# LED_Fret.net
KiCad netlist of a schematic drawn in Altium Designer
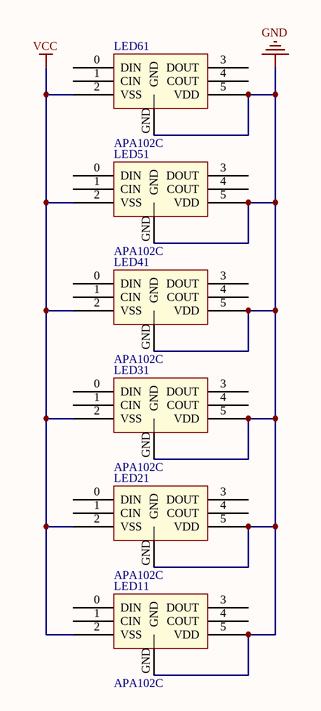
[diagram p0: LED_Fret.SchDoc]

(export (version "E")
  (design (tool "Eeschema 10.0.6"))
  (components
    (comp (ref "LED11")
      (value "APA102C")
      (footprint "RGB LED")
      (libsource (lib "Senior_SCH_Lib") (part "RGB LED"))
    )
    (comp (ref "LED21")
      (value "APA102C")
      (footprint "RGB LED")
      (libsource (lib "Senior_SCH_Lib") (part "RGB LED"))
    )
    (comp (ref "LED31")
      (value "APA102C")
      (footprint "RGB LED")
      (libsource (lib "Senior_SCH_Lib") (part "RGB LED"))
    )
    (comp (ref "LED41")
      (value "APA102C")
      (footprint "RGB LED")
      (libsource (lib "Senior_SCH_Lib") (part "RGB LED"))
    )
    (comp (ref "LED51")
      (value "APA102C")
      (footprint "RGB LED")
      (libsource (lib "Senior_SCH_Lib") (part "RGB LED"))
    )
    (comp (ref "LED61")
      (value "APA102C")
      (footprint "RGB LED")
      (libsource (lib "Senior_SCH_Lib") (part "RGB LED"))
    )
  )
  (nets
    (net (code "1") (name "GND") (class "Default")
      (node (ref "LED11") (pin "5") (pinfunction "VDD_5") (pintype "passive"))
      (node (ref "LED11") (pin "GND") (pinfunction "GND_GND") (pintype "passive"))
      (node (ref "LED21") (pin "5") (pinfunction "VDD_5") (pintype "passive"))
      (node (ref "LED21") (pin "GND") (pinfunction "GND_GND") (pintype "passive"))
      (node (ref "LED31") (pin "5") (pinfunction "VDD_5") (pintype "passive"))
      (node (ref "LED31") (pin "GND") (pinfunction "GND_GND") (pintype "passive"))
      (node (ref "LED41") (pin "5") (pinfunction "VDD_5") (pintype "passive"))
      (node (ref "LED41") (pin "GND") (pinfunction "GND_GND") (pintype "passive"))
      (node (ref "LED51") (pin "5") (pinfunction "VDD_5") (pintype "passive"))
      (node (ref "LED51") (pin "GND") (pinfunction "GND_GND") (pintype "passive"))
      (node (ref "LED61") (pin "5") (pinfunction "VDD_5") (pintype "passive"))
      (node (ref "LED61") (pin "GND") (pinfunction "GND_GND") (pintype "passive"))
    )
    (net (code "2") (name "VCC") (class "Default")
      (node (ref "LED11") (pin "2") (pinfunction "VSS_2") (pintype "passive"))
      (node (ref "LED21") (pin "2") (pinfunction "VSS_2") (pintype "passive"))
      (node (ref "LED31") (pin "2") (pinfunction "VSS_2") (pintype "passive"))
      (node (ref "LED41") (pin "2") (pinfunction "VSS_2") (pintype "passive"))
      (node (ref "LED51") (pin "2") (pinfunction "VSS_2") (pintype "passive"))
      (node (ref "LED61") (pin "2") (pinfunction "VSS_2") (pintype "passive"))
    )
    (net (code "3") (name "unconnected-(LED11-CIN-Pad1)") (class "Default")
      (node (ref "LED11") (pin "1") (pinfunction "CIN_1") (pintype "passive"))
    )
    (net (code "4") (name "unconnected-(LED11-COUT-Pad4)") (class "Default")
      (node (ref "LED11") (pin "4") (pinfunction "COUT_4") (pintype "passive"))
    )
    (net (code "5") (name "unconnected-(LED11-DIN-Pad0)") (class "Default")
      (node (ref "LED11") (pin "0") (pinfunction "DIN_0") (pintype "passive"))
    )
    (net (code "6") (name "unconnected-(LED11-DOUT-Pad3)") (class "Default")
      (node (ref "LED11") (pin "3") (pinfunction "DOUT_3") (pintype "passive"))
    )
    (net (code "7") (name "unconnected-(LED21-CIN-Pad1)") (class "Default")
      (node (ref "LED21") (pin "1") (pinfunction "CIN_1") (pintype "passive"))
    )
    (net (code "8") (name "unconnected-(LED21-COUT-Pad4)") (class "Default")
      (node (ref "LED21") (pin "4") (pinfunction "COUT_4") (pintype "passive"))
    )
    (net (code "9") (name "unconnected-(LED21-DIN-Pad0)") (class "Default")
      (node (ref "LED21") (pin "0") (pinfunction "DIN_0") (pintype "passive"))
    )
    (net (code "10") (name "unconnected-(LED21-DOUT-Pad3)") (class "Default")
      (node (ref "LED21") (pin "3") (pinfunction "DOUT_3") (pintype "passive"))
    )
    (net (code "11") (name "unconnected-(LED31-CIN-Pad1)") (class "Default")
      (node (ref "LED31") (pin "1") (pinfunction "CIN_1") (pintype "passive"))
    )
    (net (code "12") (name "unconnected-(LED31-COUT-Pad4)") (class "Default")
      (node (ref "LED31") (pin "4") (pinfunction "COUT_4") (pintype "passive"))
    )
    (net (code "13") (name "unconnected-(LED31-DIN-Pad0)") (class "Default")
      (node (ref "LED31") (pin "0") (pinfunction "DIN_0") (pintype "passive"))
    )
    (net (code "14") (name "unconnected-(LED31-DOUT-Pad3)") (class "Default")
      (node (ref "LED31") (pin "3") (pinfunction "DOUT_3") (pintype "passive"))
    )
    (net (code "15") (name "unconnected-(LED41-CIN-Pad1)") (class "Default")
      (node (ref "LED41") (pin "1") (pinfunction "CIN_1") (pintype "passive"))
    )
    (net (code "16") (name "unconnected-(LED41-COUT-Pad4)") (class "Default")
      (node (ref "LED41") (pin "4") (pinfunction "COUT_4") (pintype "passive"))
    )
    (net (code "17") (name "unconnected-(LED41-DIN-Pad0)") (class "Default")
      (node (ref "LED41") (pin "0") (pinfunction "DIN_0") (pintype "passive"))
    )
    (net (code "18") (name "unconnected-(LED41-DOUT-Pad3)") (class "Default")
      (node (ref "LED41") (pin "3") (pinfunction "DOUT_3") (pintype "passive"))
    )
    (net (code "19") (name "unconnected-(LED51-CIN-Pad1)") (class "Default")
      (node (ref "LED51") (pin "1") (pinfunction "CIN_1") (pintype "passive"))
    )
    (net (code "20") (name "unconnected-(LED51-COUT-Pad4)") (class "Default")
      (node (ref "LED51") (pin "4") (pinfunction "COUT_4") (pintype "passive"))
    )
    (net (code "21") (name "unconnected-(LED51-DIN-Pad0)") (class "Default")
      (node (ref "LED51") (pin "0") (pinfunction "DIN_0") (pintype "passive"))
    )
    (net (code "22") (name "unconnected-(LED51-DOUT-Pad3)") (class "Default")
      (node (ref "LED51") (pin "3") (pinfunction "DOUT_3") (pintype "passive"))
    )
    (net (code "23") (name "unconnected-(LED61-CIN-Pad1)") (class "Default")
      (node (ref "LED61") (pin "1") (pinfunction "CIN_1") (pintype "passive"))
    )
    (net (code "24") (name "unconnected-(LED61-COUT-Pad4)") (class "Default")
      (node (ref "LED61") (pin "4") (pinfunction "COUT_4") (pintype "passive"))
    )
    (net (code "25") (name "unconnected-(LED61-DIN-Pad0)") (class "Default")
      (node (ref "LED61") (pin "0") (pinfunction "DIN_0") (pintype "passive"))
    )
    (net (code "26") (name "unconnected-(LED61-DOUT-Pad3)") (class "Default")
      (node (ref "LED61") (pin "3") (pinfunction "DOUT_3") (pintype "passive"))
    )
  )
)
